# PowerSupply.net
KiCad netlist of a schematic drawn in Altium Designer
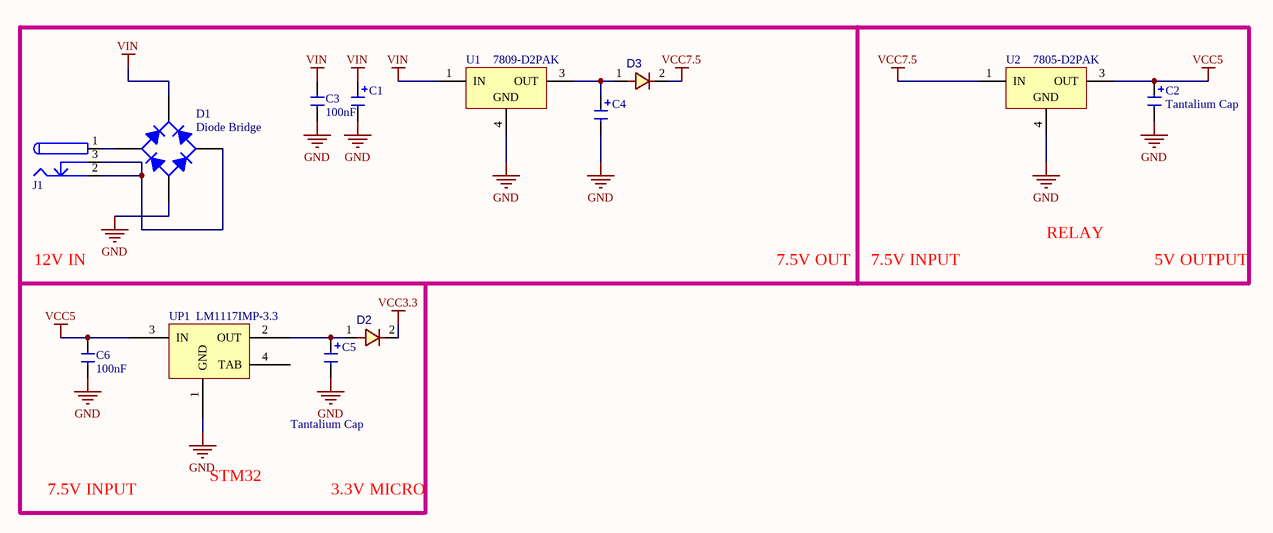
[diagram p0: PowerSupply.SchDoc]

(export (version "E")
  (design (tool "Eeschema 10.0.6"))
  (components
    (comp (ref "C1")
      (value "~")
      (footprint "CAPACITOR RADIAL SMT size F")
      (libsource (lib "ZetaBoard_Lib") (part "Capacitor Tantalium"))
    )
    (comp (ref "C2")
      (value "Tantalium Cap")
      (footprint "Tantalium Size B")
      (libsource (lib "ZetaBoard_Lib") (part "Capacitor Tantalium"))
    )
    (comp (ref "C3")
      (value "Capacitor SMD")
      (footprint "1206 Capacitor")
      (fields (field (name "ALTIUM_UNNAMED_1") "100nF"))
      (libsource (lib "ZetaBoard_Lib") (part "Capacitor SMD"))
    )
    (comp (ref "C4")
      (value "~")
      (footprint "CAPACITOR RADIAL SMT size F")
      (libsource (lib "ZetaBoard_Lib") (part "Capacitor Tantalium"))
    )
    (comp (ref "C5")
      (value "Tantalium Cap")
      (footprint "Tantalium Size B")
      (libsource (lib "ZetaBoard_Lib") (part "Capacitor Tantalium"))
    )
    (comp (ref "C6")
      (value "Capacitor SMD")
      (footprint "1206 Capacitor")
      (fields (field (name "ALTIUM_UNNAMED_1") "100nF"))
      (libsource (lib "ZetaBoard_Lib") (part "Capacitor SMD"))
    )
    (comp (ref "D1")
      (value "Diode Bridge")
      (footprint "Bridge Circle Package")
      (description "Full Wave Diode Bridge")
      (fields (field (name "DESIGNER") "Abbas Basereh"))
      (libsource (lib "Altium") (part "Diode Bridge TOTAL SIZE"))
    )
    (comp (ref "D2")
      (value "~")
      (footprint "D_SOD80")
      (description "DIODE, FAST SWTICHING, 0.3A, 0.5W")
      (fields (field (name "MANF") "MANF") (field (name "MANF_P#") "1N4148"))
      (libsource (lib "diode") (part "DIODE_SMD_1N4148_SOD80"))
    )
    (comp (ref "D3")
      (value "~")
      (footprint "D_SOD80")
      (description "DIODE, FAST SWTICHING, 0.3A, 0.5W")
      (fields (field (name "MANF") "MANF") (field (name "MANF_P#") "1N4148"))
      (libsource (lib "diode") (part "DIODE_SMD_1N4148_SOD80"))
    )
    (comp (ref "J1")
      (value "DC Power Jack")
      (footprint "DC Power Jack 1")
      (description "DC Power Jack. Center Pin 2.5mm. Diameter: 5.7mm")
      (fields (field (name "DESIGNER") "Ali Hafizi"))
      (libsource (lib "Altium") (part "DC Power Jack"))
    )
    (comp (ref "U1")
      (value "7809-D2PAK")
      (footprint "D2PAK TO-263")
      (libsource (lib "ZetaBoard_Lib") (part "7805-D2PAK"))
    )
    (comp (ref "U2")
      (value "7805-D2PAK")
      (footprint "D2PAK TO-263")
      (libsource (lib "ZetaBoard_Lib") (part "7805-D2PAK"))
    )
    (comp (ref "UP1")
      (value "LM1117IMP-3.3")
      (footprint "SOT223_4")
      (description "x.x Volt, 800mA Low-Dropout Linear Regulator, 4-pin SOT-223")
      (fields (field (name "Comment") "LM1117IMP-5.0") (field (name "DESIGNER") "Abbas Basereh"))
      (libsource (lib "2017AbbasBasereh9365731239 -ver1") (part "LM1117IMP-x.x"))
    )
  )
  (nets
    (net (code "1") (name "GND") (class "Default")
      (node (ref "C1") (pin "2") (pintype "passive"))
      (node (ref "C2") (pin "2") (pintype "passive"))
      (node (ref "C3") (pin "1") (pintype "passive"))
      (node (ref "C4") (pin "2") (pintype "passive"))
      (node (ref "C5") (pin "2") (pintype "passive"))
      (node (ref "C6") (pin "1") (pintype "passive"))
      (node (ref "D1") (pin "3") (pinfunction "AC_3") (pintype "passive"))
      (node (ref "U1") (pin "4") (pinfunction "GND_4") (pintype "power_in"))
      (node (ref "U2") (pin "4") (pinfunction "GND_4") (pintype "power_in"))
      (node (ref "UP1") (pin "1") (pinfunction "GND_1") (pintype "power_in"))
    )
    (net (code "2") (name "Net-(D1--)") (class "Default")
      (node (ref "D1") (pin "4") (pinfunction "-_4") (pintype "passive"))
      (node (ref "J1") (pin "2") (pinfunction "2_2") (pintype "power_in"))
      (node (ref "J1") (pin "3") (pinfunction "3_3") (pintype "power_in"))
    )
    (net (code "3") (name "Net-(D1-AC-Pad2)") (class "Default")
      (node (ref "D1") (pin "2") (pinfunction "AC_2") (pintype "passive"))
      (node (ref "J1") (pin "1") (pinfunction "1_1") (pintype "power_in"))
    )
    (net (code "4") (name "Net-(U1-OUT)") (class "Default")
      (node (ref "C4") (pin "1") (pintype "passive"))
      (node (ref "D3") (pin "1") (pinfunction "1_1") (pintype "passive"))
      (node (ref "U1") (pin "3") (pinfunction "OUT_3") (pintype "power_in"))
    )
    (net (code "5") (name "Net-(UP1-OUT)") (class "Default")
      (node (ref "C5") (pin "1") (pintype "passive"))
      (node (ref "D2") (pin "1") (pinfunction "1_1") (pintype "passive"))
      (node (ref "UP1") (pin "2") (pinfunction "OUT_2") (pintype "power_in"))
    )
    (net (code "6") (name "VCC3.3") (class "Default")
      (node (ref "D2") (pin "2") (pinfunction "2_2") (pintype "passive"))
    )
    (net (code "7") (name "VCC5") (class "Default")
      (node (ref "C2") (pin "1") (pintype "passive"))
      (node (ref "C6") (pin "2") (pintype "passive"))
      (node (ref "U2") (pin "3") (pinfunction "OUT_3") (pintype "power_in"))
      (node (ref "UP1") (pin "3") (pinfunction "IN_3") (pintype "power_in"))
    )
    (net (code "8") (name "VCC7.5") (class "Default")
      (node (ref "D3") (pin "2") (pinfunction "2_2") (pintype "passive"))
      (node (ref "U2") (pin "1") (pinfunction "IN_1") (pintype "power_in"))
    )
    (net (code "9") (name "VIN") (class "Default")
      (node (ref "C1") (pin "1") (pintype "passive"))
      (node (ref "C3") (pin "2") (pintype "passive"))
      (node (ref "D1") (pin "1") (pinfunction "+_1") (pintype "passive"))
      (node (ref "U1") (pin "1") (pinfunction "IN_1") (pintype "power_in"))
    )
    (net (code "10") (name "unconnected-(UP1-TAB-Pad4)") (class "Default")
      (node (ref "UP1") (pin "4") (pinfunction "TAB_4") (pintype "power_in"))
    )
  )
)
